# AMS5047p.net
KiCad netlist of a schematic drawn in EAGLE
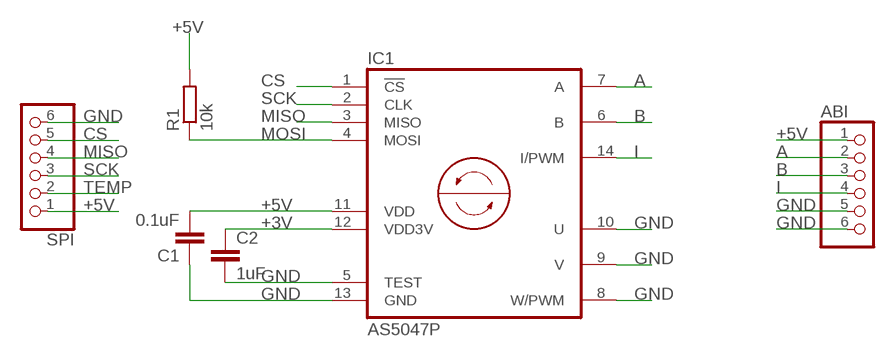
[diagram p0: schematic, sheet 1]

(export (version "E")
  (design (tool "Eeschema 10.0.6"))
  (components
    (comp (ref "ABI")
      (value "PINHD-1X6")
      (footprint "eagle-import:1X06")
      (libsource (lib "eagle-import") (part "PINHD-1X6"))
    )
    (comp (ref "C1")
      (value "0.1uF")
      (footprint "eagle-import:C0603")
      (libsource (lib "eagle-import") (part "C-EUC0603"))
    )
    (comp (ref "C2")
      (value "1uF")
      (footprint "eagle-import:C0603")
      (libsource (lib "eagle-import") (part "C-EUC0603"))
    )
    (comp (ref "IC1")
      (value "AS5047P")
      (footprint "eagle-import:TSSOP14")
      (libsource (lib "eagle-import") (part "AS5047P"))
    )
    (comp (ref "R1")
      (value "10k")
      (footprint "eagle-import:R0603")
      (libsource (lib "eagle-import") (part "R-EU_R0603"))
    )
    (comp (ref "SPI")
      (value "PINHD-1X6")
      (footprint "eagle-import:1X06")
      (libsource (lib "eagle-import") (part "PINHD-1X6"))
    )
  )
  (nets
    (net (code "1") (name "/+3V") (class "Default")
      (node (ref "C2") (pin "1") (pinfunction "1_1") (pintype "passive"))
      (node (ref "IC1") (pin "12") (pinfunction "VDD3V_12") (pintype "power_in"))
    )
    (net (code "2") (name "/+5V") (class "Default")
      (node (ref "ABI") (pin "1") (pinfunction "1_1") (pintype "passive"))
      (node (ref "C1") (pin "2") (pinfunction "2_2") (pintype "passive"))
      (node (ref "IC1") (pin "11") (pinfunction "VDD_11") (pintype "power_in"))
      (node (ref "R1") (pin "2") (pinfunction "2_2") (pintype "passive"))
      (node (ref "SPI") (pin "1") (pinfunction "1_1") (pintype "passive"))
    )
    (net (code "3") (name "/A") (class "Default")
      (node (ref "ABI") (pin "2") (pinfunction "2_2") (pintype "passive"))
      (node (ref "IC1") (pin "7") (pinfunction "A_7") (pintype "output"))
    )
    (net (code "4") (name "/B") (class "Default")
      (node (ref "ABI") (pin "3") (pinfunction "3_3") (pintype "passive"))
      (node (ref "IC1") (pin "6") (pinfunction "B_6") (pintype "output"))
    )
    (net (code "5") (name "/CS") (class "Default")
      (node (ref "IC1") (pin "1") (pinfunction "~{CS}_1") (pintype "input"))
      (node (ref "SPI") (pin "5") (pinfunction "5_5") (pintype "passive"))
    )
    (net (code "6") (name "/GND") (class "Default")
      (node (ref "ABI") (pin "5") (pinfunction "5_5") (pintype "passive"))
      (node (ref "ABI") (pin "6") (pinfunction "6_6") (pintype "passive"))
      (node (ref "C1") (pin "1") (pinfunction "1_1") (pintype "passive"))
      (node (ref "C2") (pin "2") (pinfunction "2_2") (pintype "passive"))
      (node (ref "IC1") (pin "10") (pinfunction "U_10") (pintype "output"))
      (node (ref "IC1") (pin "13") (pinfunction "GND_13") (pintype "power_in"))
      (node (ref "IC1") (pin "5") (pinfunction "TEST_5") (pintype "input"))
      (node (ref "IC1") (pin "8") (pinfunction "W/PWM_8") (pintype "output"))
      (node (ref "IC1") (pin "9") (pinfunction "V_9") (pintype "output"))
      (node (ref "SPI") (pin "6") (pinfunction "6_6") (pintype "passive"))
    )
    (net (code "7") (name "/I") (class "Default")
      (node (ref "ABI") (pin "4") (pinfunction "4_4") (pintype "passive"))
      (node (ref "IC1") (pin "14") (pinfunction "I/PWM_14") (pintype "output"))
    )
    (net (code "8") (name "/MISO") (class "Default")
      (node (ref "IC1") (pin "3") (pinfunction "MISO_3") (pintype "output"))
      (node (ref "SPI") (pin "4") (pinfunction "4_4") (pintype "passive"))
    )
    (net (code "9") (name "/MOSI") (class "Default")
      (node (ref "IC1") (pin "4") (pinfunction "MOSI_4") (pintype "input"))
      (node (ref "R1") (pin "1") (pinfunction "1_1") (pintype "passive"))
    )
    (net (code "10") (name "/SCK") (class "Default")
      (node (ref "IC1") (pin "2") (pinfunction "CLK_2") (pintype "input"))
      (node (ref "SPI") (pin "3") (pinfunction "3_3") (pintype "passive"))
    )
    (net (code "11") (name "/TEMP") (class "Default")
      (node (ref "SPI") (pin "2") (pinfunction "2_2") (pintype "passive"))
    )
  )
)
